# secondary_LTC.net
KiCad netlist of a schematic drawn in Altium Designer
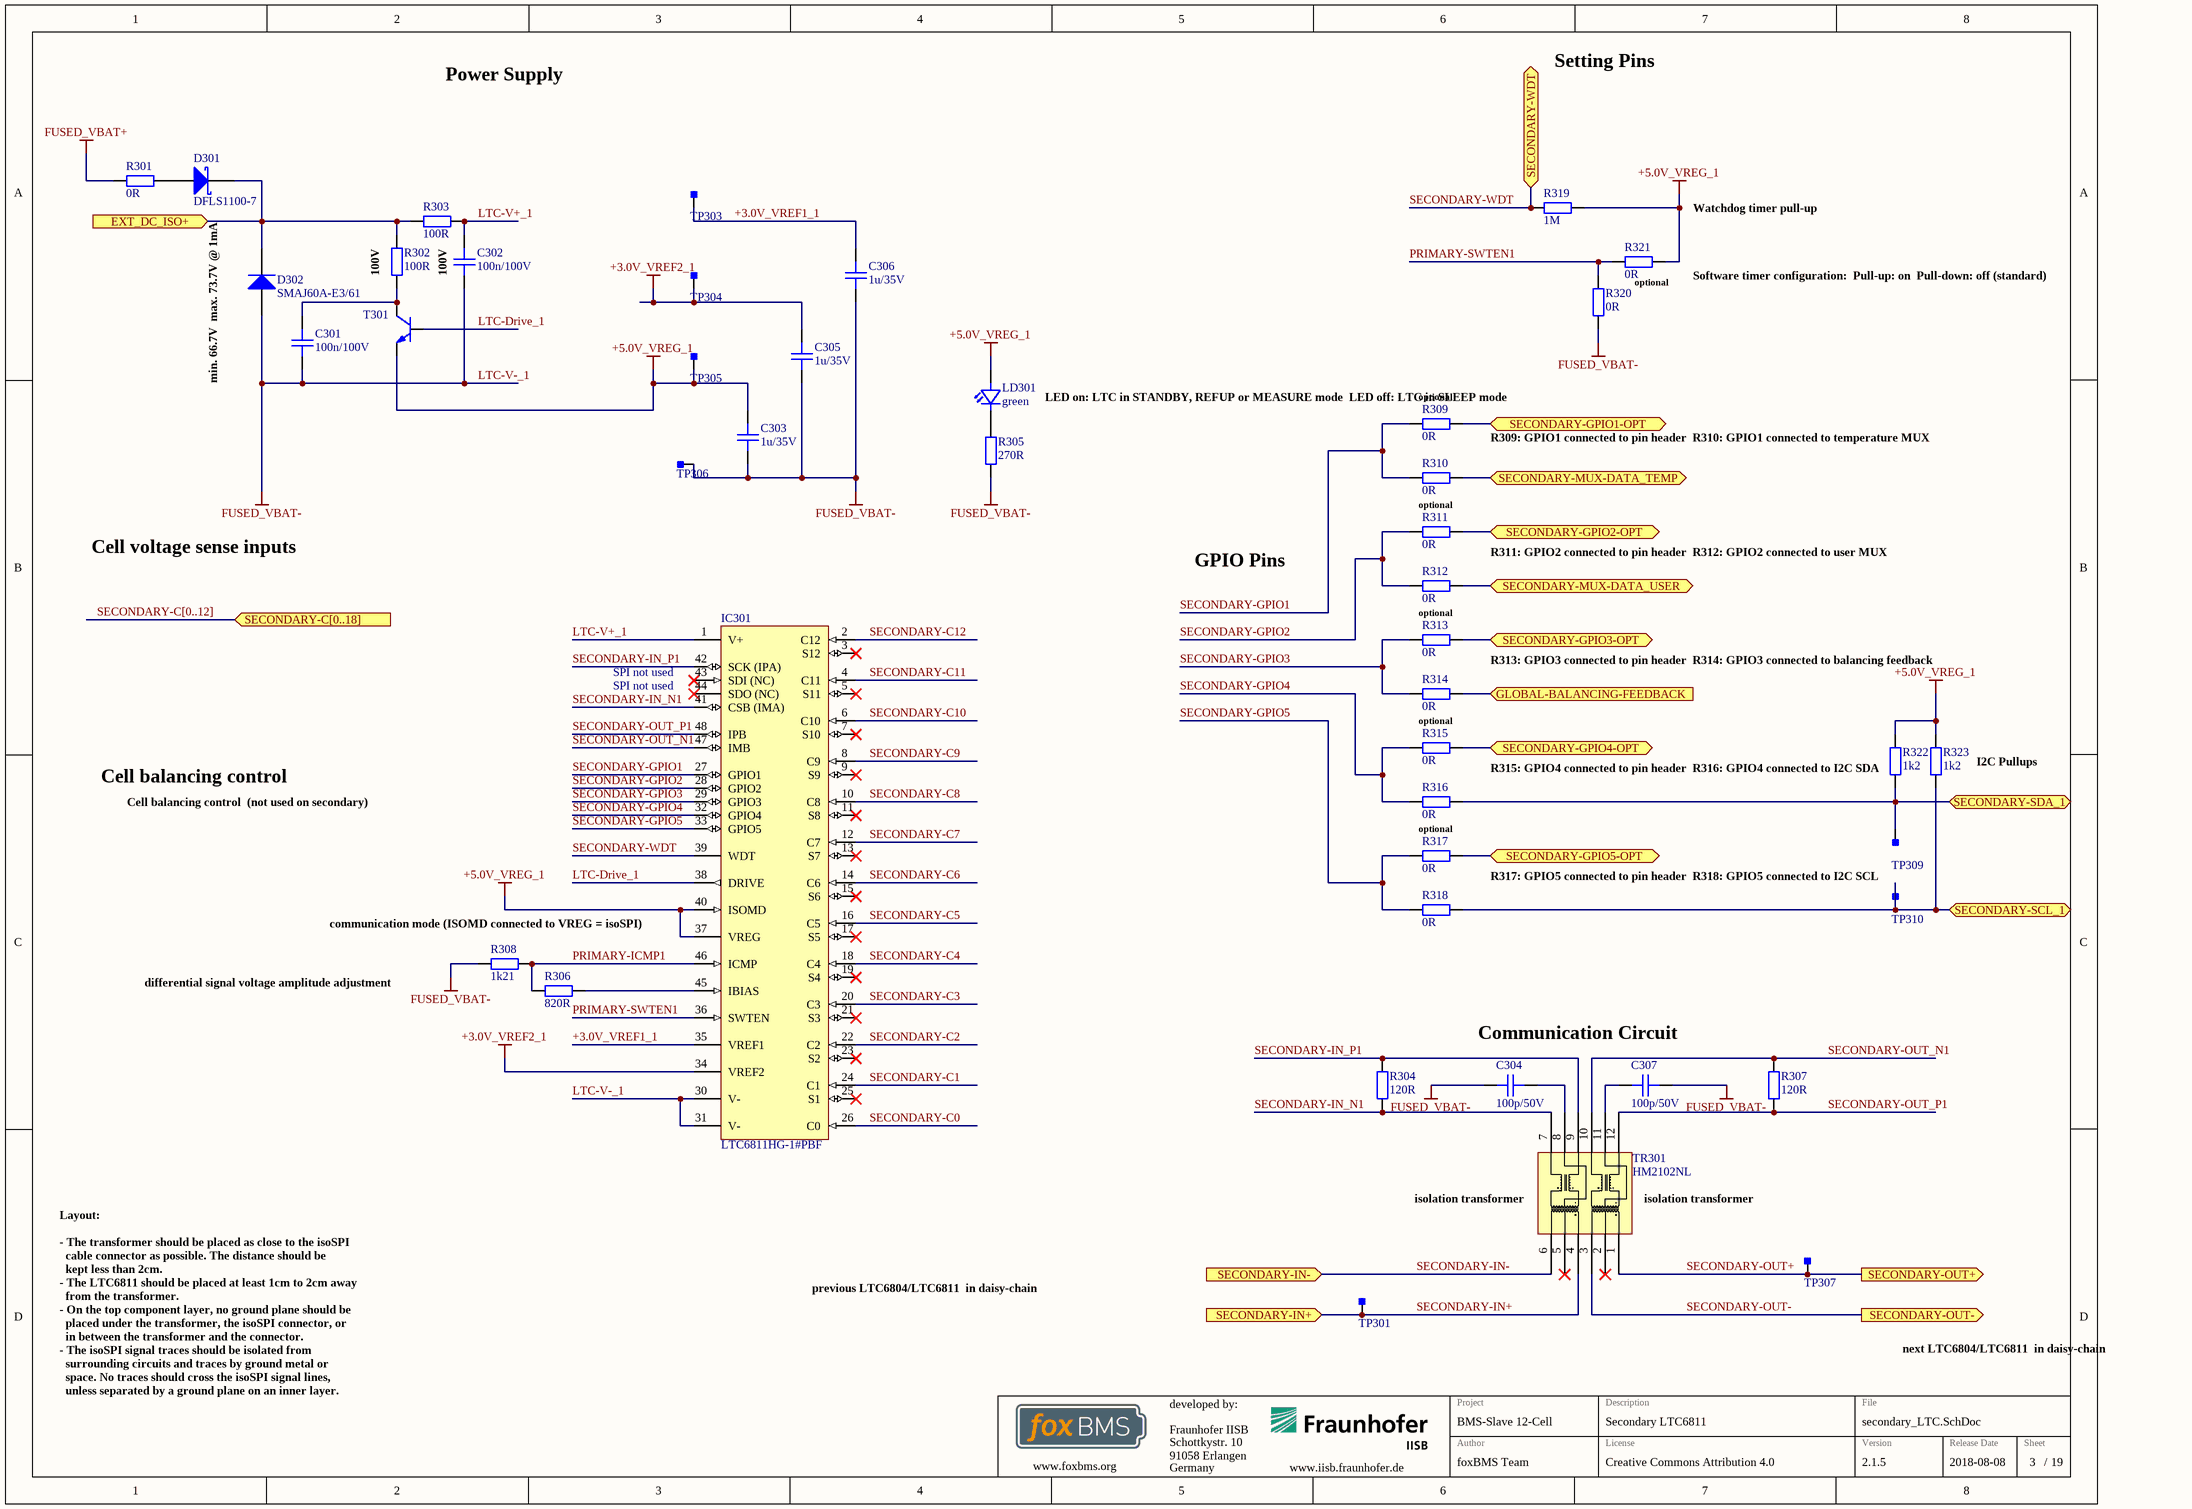
[diagram p0: secondary_LTC.SchDoc]

(export (version "E")
  (design (tool "Eeschema 10.0.6"))
  (components
    (comp (ref "C301")
      (value "100n/100V")
      (footprint "CAPC2012X14N")
      (description "MLCC")
      (fields (field (name "PART NUMBER") "gen_C_ceramic_100n_100V_X7R_0805"))
      (libsource (lib "OE750") (part "C"))
    )
    (comp (ref "C302")
      (value "100n/100V")
      (footprint "CAPC2012X14N")
      (description "MLCC")
      (fields (field (name "PART NUMBER") "gen_C_ceramic_100n_100V_X7R_0805"))
      (libsource (lib "OE750") (part "C"))
    )
    (comp (ref "C303")
      (value "1u/35V")
      (footprint "CAPC1608X08N")
      (description "MLCC")
      (fields (field (name "PART NUMBER") "gen_C_ceramic_1u_35V_X7R_0603"))
      (libsource (lib "OE750") (part "C"))
    )
    (comp (ref "C304")
      (value "100p/50V")
      (footprint "CAPC1608X08N")
      (description "MLCC")
      (fields (field (name "PART NUMBER") "gen_C_ceramic_100p_50V_C0G_0603"))
      (libsource (lib "OE750") (part "C"))
    )
    (comp (ref "C305")
      (value "1u/35V")
      (footprint "CAPC1608X08N")
      (description "MLCC")
      (fields (field (name "PART NUMBER") "gen_C_ceramic_1u_35V_X7R_0603"))
      (libsource (lib "OE750") (part "C"))
    )
    (comp (ref "C306")
      (value "1u/35V")
      (footprint "CAPC1608X08N")
      (description "MLCC")
      (fields (field (name "PART NUMBER") "gen_C_ceramic_1u_35V_X7R_0603"))
      (libsource (lib "OE750") (part "C"))
    )
    (comp (ref "C307")
      (value "100p/50V")
      (footprint "CAPC1608X08N")
      (description "MLCC")
      (fields (field (name "PART NUMBER") "gen_C_ceramic_100p_50V_C0G_0603"))
      (libsource (lib "OE750") (part "C"))
    )
    (comp (ref "D301")
      (value "DFLS1100-7")
      (footprint "DIOD-POWERDI123-2_V")
      (fields (field (name "MANUFACTURER") "Diodes Inc"))
      (libsource (lib "Altium Content Vault") (part "DSKY-AK-2"))
    )
    (comp (ref "D302")
      (value "SMAJ60A-E3/61")
      (footprint "VISH-DO-214AC-2_N")
      (fields (field (name "MANUFACTURER") "Vishay Semiconductor"))
      (libsource (lib "Altium Content Vault") (part "VISH-K1A2-2"))
    )
    (comp (ref "IC301")
      (value "LTC6811HG-1#PBF")
      (footprint "LT-G-48_L")
      (description "Multicell Battery Monitor, 60 V Vin MAX, 48-pin SOP (G-48), -40 to 125 degC, Pb-Free")
      (fields (field (name "MANUFACTURER") "Linear Technology"))
      (libsource (lib "OE750") (part "LTC6811HG-1#PBF"))
    )
    (comp (ref "LD301")
      (value "green")
      (footprint "LEDC1608X07N")
      (description "LED")
      (fields (field (name "PART NUMBER") "gen_LED_0603_green"))
      (libsource (lib "OE750") (part "D_LED"))
    )
    (comp (ref "R301")
      (value "0R")
      (footprint "RESC2012X05N")
      (description "SMD Resistor 0R 0805")
      (fields (field (name "PART NUMBER") "gen_R_0R_0805") (field (name "POWER") "0.125W"))
      (libsource (lib "OE750") (part "R"))
    )
    (comp (ref "R302")
      (value "100R")
      (footprint "RESC2012X05N")
      (description "SMD Resistor 100R 0805")
      (fields (field (name "PART NUMBER") "gen_R_100R_0805") (field (name "TOLERANCE") "1%"))
      (libsource (lib "OE750") (part "R"))
    )
    (comp (ref "R303")
      (value "100R")
      (footprint "RESC2012X05N")
      (description "SMD Resistor 100R 0805")
      (fields (field (name "PART NUMBER") "gen_R_100R_0805") (field (name "TOLERANCE") "1%"))
      (libsource (lib "OE750") (part "R"))
    )
    (comp (ref "R304")
      (value "120R")
      (footprint "RESC1608X05N")
      (description "SMD Resistor 120R 0603")
      (fields (field (name "PART NUMBER") "gen_R_120R_0603") (field (name "TOLERANCE") "1%"))
      (libsource (lib "OE750") (part "R"))
    )
    (comp (ref "R305")
      (value "270R")
      (footprint "RESC1608X05N")
      (description "SMD Resistor 270R 0603")
      (fields (field (name "PART NUMBER") "gen_R_270R_0603") (field (name "TOLERANCE") "1%"))
      (libsource (lib "OE750") (part "R"))
    )
    (comp (ref "R306")
      (value "820R")
      (footprint "RESC1608X05N")
      (description "SMD Resistor 820R 0603")
      (fields (field (name "PART NUMBER") "gen_R_820R_0603") (field (name "TOLERANCE") "1%"))
      (libsource (lib "OE750") (part "R"))
    )
    (comp (ref "R307")
      (value "120R")
      (footprint "RESC1608X05N")
      (description "SMD Resistor 120R 0603")
      (fields (field (name "PART NUMBER") "gen_R_120R_0603") (field (name "TOLERANCE") "1%"))
      (libsource (lib "OE750") (part "R"))
    )
    (comp (ref "R308")
      (value "1k21")
      (footprint "RESC1608X05N")
      (description "SMD Resistor 1k21 0603")
      (fields (field (name "PART NUMBER") "gen_R_1k21_0603") (field (name "TOLERANCE") "1%"))
      (libsource (lib "OE750") (part "R"))
    )
    (comp (ref "R309")
      (value "0R")
      (footprint "RESC1608X05N")
      (description "SMD Resistor 0R 0603")
      (fields (field (name "PART NUMBER") "gen_R_0R_0603") (field (name "POWER") "0.1W"))
      (libsource (lib "OE750") (part "R"))
    )
    (comp (ref "R310")
      (value "0R")
      (footprint "RESC1608X05N")
      (description "SMD Resistor 0R 0603")
      (fields (field (name "PART NUMBER") "gen_R_0R_0603") (field (name "POWER") "0.1W"))
      (libsource (lib "OE750") (part "R"))
    )
    (comp (ref "R311")
      (value "0R")
      (footprint "RESC1608X05N")
      (description "SMD Resistor 0R 0603")
      (fields (field (name "PART NUMBER") "gen_R_0R_0603") (field (name "POWER") "0.1W"))
      (libsource (lib "OE750") (part "R"))
    )
    (comp (ref "R312")
      (value "0R")
      (footprint "RESC1608X05N")
      (description "SMD Resistor 0R 0603")
      (fields (field (name "PART NUMBER") "gen_R_0R_0603") (field (name "POWER") "0.1W"))
      (libsource (lib "OE750") (part "R"))
    )
    (comp (ref "R313")
      (value "0R")
      (footprint "RESC1608X05N")
      (description "SMD Resistor 0R 0603")
      (fields (field (name "PART NUMBER") "gen_R_0R_0603") (field (name "POWER") "0.1W"))
      (libsource (lib "OE750") (part "R"))
    )
    (comp (ref "R314")
      (value "0R")
      (footprint "RESC1608X05N")
      (description "SMD Resistor 0R 0603")
      (fields (field (name "PART NUMBER") "gen_R_0R_0603") (field (name "POWER") "0.1W"))
      (libsource (lib "OE750") (part "R"))
    )
    (comp (ref "R315")
      (value "0R")
      (footprint "RESC1608X05N")
      (description "SMD Resistor 0R 0603")
      (fields (field (name "PART NUMBER") "gen_R_0R_0603") (field (name "POWER") "0.1W"))
      (libsource (lib "OE750") (part "R"))
    )
    (comp (ref "R316")
      (value "0R")
      (footprint "RESC1608X05N")
      (description "SMD Resistor 0R 0603")
      (fields (field (name "PART NUMBER") "gen_R_0R_0603") (field (name "POWER") "0.1W"))
      (libsource (lib "OE750") (part "R"))
    )
    (comp (ref "R317")
      (value "0R")
      (footprint "RESC1608X05N")
      (description "SMD Resistor 0R 0603")
      (fields (field (name "PART NUMBER") "gen_R_0R_0603") (field (name "POWER") "0.1W"))
      (libsource (lib "OE750") (part "R"))
    )
    (comp (ref "R318")
      (value "0R")
      (footprint "RESC1608X05N")
      (description "SMD Resistor 0R 0603")
      (fields (field (name "PART NUMBER") "gen_R_0R_0603") (field (name "POWER") "0.1W"))
      (libsource (lib "OE750") (part "R"))
    )
    (comp (ref "R319")
      (value "1M")
      (footprint "RESC1608X05N")
      (description "SMD Resistor 1M 0603")
      (fields (field (name "PART NUMBER") "gen_R_1M_0603") (field (name "TOLERANCE") "1%"))
      (libsource (lib "OE750") (part "R"))
    )
    (comp (ref "R320")
      (value "0R")
      (footprint "RESC1608X05N")
      (description "SMD Resistor 0R 0603")
      (fields (field (name "PART NUMBER") "gen_R_0R_0603") (field (name "POWER") "0.1W"))
      (libsource (lib "OE750") (part "R"))
    )
    (comp (ref "R321")
      (value "0R")
      (footprint "RESC1608X05N")
      (description "SMD Resistor 0R 0603")
      (fields (field (name "PART NUMBER") "gen_R_0R_0603") (field (name "POWER") "0.1W"))
      (libsource (lib "OE750") (part "R"))
    )
    (comp (ref "R322")
      (value "1k2")
      (footprint "RESC1608X05N")
      (description "SMD Resistor 1k2 0603")
      (fields (field (name "PART NUMBER") "gen_R_1k2_0603") (field (name "TOLERANCE") "1%"))
      (libsource (lib "OE750") (part "R"))
    )
    (comp (ref "R323")
      (value "1k2")
      (footprint "RESC1608X05N")
      (description "SMD Resistor 1k2 0603")
      (fields (field (name "PART NUMBER") "gen_R_1k2_0603") (field (name "TOLERANCE") "1%"))
      (libsource (lib "OE750") (part "R"))
    )
    (comp (ref "T301")
      (value "PBHV8115Z")
      (footprint "SOT230P700X180-4N")
      (description "150 V, 1 A NPN high-voltage low V\r\nCEsat\r\n (BISS) transistor")
      (fields (field (name "MANUFACTURER") "Nexperia"))
      (libsource (lib "OE750") (part "NPN_4_PIN"))
    )
    (comp (ref "TP301")
      (value "Testpoint_Square")
      (footprint "Testpoint_S1")
      (description "Testpoint, square")
      (libsource (lib "OE750") (part "Testpoint_Square"))
    )
    (comp (ref "TP303")
      (value "Testpoint_Square")
      (footprint "Testpoint_S1")
      (description "Testpoint, square")
      (libsource (lib "OE750") (part "Testpoint_Square"))
    )
    (comp (ref "TP304")
      (value "Testpoint_Square")
      (footprint "Testpoint_S1")
      (description "Testpoint, square")
      (libsource (lib "OE750") (part "Testpoint_Square"))
    )
    (comp (ref "TP305")
      (value "Testpoint_Square")
      (footprint "Testpoint_S1")
      (description "Testpoint, square")
      (libsource (lib "OE750") (part "Testpoint_Square"))
    )
    (comp (ref "TP306")
      (value "Testpoint_Square")
      (footprint "Testpoint_S1")
      (description "Testpoint, square")
      (libsource (lib "OE750") (part "Testpoint_Square"))
    )
    (comp (ref "TP307")
      (value "Testpoint_Square")
      (footprint "Testpoint_S1")
      (description "Testpoint, square")
      (libsource (lib "OE750") (part "Testpoint_Square"))
    )
    (comp (ref "TP309")
      (value "Testpoint_Square")
      (footprint "Testpoint_S1")
      (description "Testpoint, square")
      (libsource (lib "OE750") (part "Testpoint_Square"))
    )
    (comp (ref "TP310")
      (value "Testpoint_Square")
      (footprint "Testpoint_S1")
      (description "Testpoint, square")
      (libsource (lib "OE750") (part "Testpoint_Square"))
    )
    (comp (ref "TR301")
      (value "HM2102NL")
      (footprint "HM2102NL")
      (description "Pulse HM2102NL BMS Transformer")
      (fields (field (name "MANUFACTURER") "Pulse"))
      (libsource (lib "OE750") (part "HM2102NL"))
    )
  )
  (nets
    (net (code "1") (name "+3.0V_VREF2_1") (class "Default")
      (node (ref "C305") (pin "2") (pinfunction "2_2") (pintype "passive"))
      (node (ref "IC301") (pin "34") (pinfunction "VREF2_34") (pintype "passive"))
      (node (ref "TP304") (pin "1") (pinfunction "1_1") (pintype "passive"))
    )
    (net (code "2") (name "+5.0V_VREG_1") (class "Default")
      (node (ref "C303") (pin "2") (pinfunction "2_2") (pintype "passive"))
      (node (ref "IC301") (pin "37") (pinfunction "VREG_37") (pintype "power_in"))
      (node (ref "IC301") (pin "40") (pinfunction "ISOMD_40") (pintype "input"))
      (node (ref "LD301") (pin "2") (pinfunction "A_2") (pintype "passive"))
      (node (ref "R319") (pin "2") (pinfunction "2_2") (pintype "passive"))
      (node (ref "R321") (pin "2") (pinfunction "2_2") (pintype "passive"))
      (node (ref "R322") (pin "2") (pinfunction "2_2") (pintype "passive"))
      (node (ref "R323") (pin "2") (pinfunction "2_2") (pintype "passive"))
      (node (ref "T301") (pin "3") (pinfunction "E_3") (pintype "passive"))
      (node (ref "TP305") (pin "1") (pinfunction "1_1") (pintype "passive"))
    )
    (net (code "3") (name "/+3.0V_VREF1_1") (class "Default")
      (node (ref "C306") (pin "2") (pinfunction "2_2") (pintype "passive"))
      (node (ref "IC301") (pin "35") (pinfunction "VREF1_35") (pintype "passive"))
      (node (ref "TP303") (pin "1") (pinfunction "1_1") (pintype "passive"))
    )
    (net (code "4") (name "/EXT_DC_ISO+") (class "Default")
      (node (ref "D301") (pin "2") (pinfunction "K_2") (pintype "passive"))
      (node (ref "D302") (pin "1") (pinfunction "K_1") (pintype "passive"))
      (node (ref "R302") (pin "2") (pinfunction "2_2") (pintype "passive"))
      (node (ref "R303") (pin "1") (pinfunction "1_1") (pintype "passive"))
    )
    (net (code "5") (name "/GLOBAL-BALANCING-FEEDBACK") (class "Default")
      (node (ref "R314") (pin "1") (pinfunction "1_1") (pintype "passive"))
    )
    (net (code "6") (name "/LTC-Drive_1") (class "Default")
      (node (ref "IC301") (pin "38") (pinfunction "DRIVE_38") (pintype "output"))
      (node (ref "T301") (pin "1") (pinfunction "B_1") (pintype "passive"))
    )
    (net (code "7") (name "/LTC-V+_1") (class "Default")
      (node (ref "C302") (pin "1") (pinfunction "1_1") (pintype "passive"))
      (node (ref "IC301") (pin "1") (pinfunction "V+_1") (pintype "power_in"))
      (node (ref "R303") (pin "2") (pinfunction "2_2") (pintype "passive"))
    )
    (net (code "8") (name "/PRIMARY-ICMP1") (class "Default")
      (node (ref "IC301") (pin "46") (pinfunction "ICMP_46") (pintype "input"))
      (node (ref "R306") (pin "1") (pinfunction "1_1") (pintype "passive"))
      (node (ref "R308") (pin "2") (pinfunction "2_2") (pintype "passive"))
    )
    (net (code "9") (name "/PRIMARY-SWTEN1") (class "Default")
      (node (ref "IC301") (pin "36") (pinfunction "SWTEN_36") (pintype "input"))
      (node (ref "R320") (pin "2") (pinfunction "2_2") (pintype "passive"))
      (node (ref "R321") (pin "1") (pinfunction "1_1") (pintype "passive"))
    )
    (net (code "10") (name "/SECONDARY-C0") (class "Default")
      (node (ref "IC301") (pin "26") (pinfunction "C0_26") (pintype "input"))
    )
    (net (code "11") (name "/SECONDARY-C1") (class "Default")
      (node (ref "IC301") (pin "24") (pinfunction "C1_24") (pintype "input"))
    )
    (net (code "12") (name "/SECONDARY-C2") (class "Default")
      (node (ref "IC301") (pin "22") (pinfunction "C2_22") (pintype "input"))
    )
    (net (code "13") (name "/SECONDARY-C3") (class "Default")
      (node (ref "IC301") (pin "20") (pinfunction "C3_20") (pintype "input"))
    )
    (net (code "14") (name "/SECONDARY-C4") (class "Default")
      (node (ref "IC301") (pin "18") (pinfunction "C4_18") (pintype "input"))
    )
    (net (code "15") (name "/SECONDARY-C5") (class "Default")
      (node (ref "IC301") (pin "16") (pinfunction "C5_16") (pintype "input"))
    )
    (net (code "16") (name "/SECONDARY-C6") (class "Default")
      (node (ref "IC301") (pin "14") (pinfunction "C6_14") (pintype "input"))
    )
    (net (code "17") (name "/SECONDARY-C7") (class "Default")
      (node (ref "IC301") (pin "12") (pinfunction "C7_12") (pintype "input"))
    )
    (net (code "18") (name "/SECONDARY-C8") (class "Default")
      (node (ref "IC301") (pin "10") (pinfunction "C8_10") (pintype "input"))
    )
    (net (code "19") (name "/SECONDARY-C9") (class "Default")
      (node (ref "IC301") (pin "8") (pinfunction "C9_8") (pintype "input"))
    )
    (net (code "20") (name "/SECONDARY-C10") (class "Default")
      (node (ref "IC301") (pin "6") (pinfunction "C10_6") (pintype "input"))
    )
    (net (code "21") (name "/SECONDARY-C11") (class "Default")
      (node (ref "IC301") (pin "4") (pinfunction "C11_4") (pintype "input"))
    )
    (net (code "22") (name "/SECONDARY-C12") (class "Default")
      (node (ref "IC301") (pin "2") (pinfunction "C12_2") (pintype "input"))
    )
    (net (code "24") (name "/SECONDARY-GPIO1") (class "Default")
      (node (ref "IC301") (pin "27") (pinfunction "GPIO1_27") (pintype "bidirectional"))
      (node (ref "R309") (pin "2") (pinfunction "2_2") (pintype "passive"))
      (node (ref "R310") (pin "2") (pinfunction "2_2") (pintype "passive"))
    )
    (net (code "25") (name "/SECONDARY-GPIO1-OPT") (class "Default")
      (node (ref "R309") (pin "1") (pinfunction "1_1") (pintype "passive"))
    )
    (net (code "26") (name "/SECONDARY-GPIO2") (class "Default")
      (node (ref "IC301") (pin "28") (pinfunction "GPIO2_28") (pintype "bidirectional"))
      (node (ref "R311") (pin "2") (pinfunction "2_2") (pintype "passive"))
      (node (ref "R312") (pin "2") (pinfunction "2_2") (pintype "passive"))
    )
    (net (code "27") (name "/SECONDARY-GPIO2-OPT") (class "Default")
      (node (ref "R311") (pin "1") (pinfunction "1_1") (pintype "passive"))
    )
    (net (code "28") (name "/SECONDARY-GPIO3") (class "Default")
      (node (ref "IC301") (pin "29") (pinfunction "GPIO3_29") (pintype "bidirectional"))
      (node (ref "R313") (pin "2") (pinfunction "2_2") (pintype "passive"))
      (node (ref "R314") (pin "2") (pinfunction "2_2") (pintype "passive"))
    )
    (net (code "29") (name "/SECONDARY-GPIO3-OPT") (class "Default")
      (node (ref "R313") (pin "1") (pinfunction "1_1") (pintype "passive"))
    )
    (net (code "30") (name "/SECONDARY-GPIO4") (class "Default")
      (node (ref "IC301") (pin "32") (pinfunction "GPIO4_32") (pintype "bidirectional"))
      (node (ref "R315") (pin "2") (pinfunction "2_2") (pintype "passive"))
      (node (ref "R316") (pin "2") (pinfunction "2_2") (pintype "passive"))
    )
    (net (code "31") (name "/SECONDARY-GPIO4-OPT") (class "Default")
      (node (ref "R315") (pin "1") (pinfunction "1_1") (pintype "passive"))
    )
    (net (code "32") (name "/SECONDARY-GPIO5") (class "Default")
      (node (ref "IC301") (pin "33") (pinfunction "GPIO5_33") (pintype "bidirectional"))
      (node (ref "R317") (pin "2") (pinfunction "2_2") (pintype "passive"))
      (node (ref "R318") (pin "2") (pinfunction "2_2") (pintype "passive"))
    )
    (net (code "33") (name "/SECONDARY-GPIO5-OPT") (class "Default")
      (node (ref "R317") (pin "1") (pinfunction "1_1") (pintype "passive"))
    )
    (net (code "34") (name "/SECONDARY-IN+") (class "Default")
      (node (ref "TP301") (pin "1") (pinfunction "1_1") (pintype "passive"))
      (node (ref "TR301") (pin "4") (pintype "passive"))
    )
    (net (code "35") (name "/SECONDARY-IN-") (class "Default")
      (node (ref "TR301") (pin "6") (pintype "passive"))
    )
    (net (code "36") (name "/SECONDARY-IN_N1") (class "Default")
      (node (ref "IC301") (pin "41") (pinfunction "CSB_(IMA)_41") (pintype "bidirectional"))
      (node (ref "R304") (pin "2") (pinfunction "2_2") (pintype "passive"))
      (node (ref "TR301") (pin "7") (pintype "passive"))
    )
    (net (code "37") (name "/SECONDARY-IN_P1") (class "Default")
      (node (ref "IC301") (pin "42") (pinfunction "SCK_(IPA)_42") (pintype "bidirectional"))
      (node (ref "R304") (pin "1") (pinfunction "1_1") (pintype "passive"))
      (node (ref "TR301") (pin "9") (pintype "passive"))
    )
    (net (code "38") (name "/SECONDARY-MUX-DATA_TEMP") (class "Default")
      (node (ref "R310") (pin "1") (pinfunction "1_1") (pintype "passive"))
    )
    (net (code "39") (name "/SECONDARY-MUX-DATA_USER") (class "Default")
      (node (ref "R312") (pin "1") (pinfunction "1_1") (pintype "passive"))
    )
    (net (code "40") (name "/SECONDARY-OUT+") (class "Default")
      (node (ref "TP307") (pin "1") (pinfunction "1_1") (pintype "passive"))
      (node (ref "TR301") (pin "1") (pintype "passive"))
    )
    (net (code "41") (name "/SECONDARY-OUT-") (class "Default")
      (node (ref "TR301") (pin "3") (pintype "passive"))
    )
    (net (code "42") (name "/SECONDARY-OUT_N1") (class "Default")
      (node (ref "IC301") (pin "47") (pinfunction "IMB_47") (pintype "bidirectional"))
      (node (ref "R307") (pin "2") (pinfunction "2_2") (pintype "passive"))
      (node (ref "TR301") (pin "10") (pintype "passive"))
    )
    (net (code "43") (name "/SECONDARY-OUT_P1") (class "Default")
      (node (ref "IC301") (pin "48") (pinfunction "IPB_48") (pintype "bidirectional"))
      (node (ref "R307") (pin "1") (pinfunction "1_1") (pintype "passive"))
      (node (ref "TR301") (pin "12") (pintype "passive"))
    )
    (net (code "44") (name "/SECONDARY-SCL_1") (class "Default")
      (node (ref "R318") (pin "1") (pinfunction "1_1") (pintype "passive"))
      (node (ref "R323") (pin "1") (pinfunction "1_1") (pintype "passive"))
      (node (ref "TP310") (pin "1") (pinfunction "1_1") (pintype "passive"))
    )
    (net (code "45") (name "/SECONDARY-SDA_1") (class "Default")
      (node (ref "R316") (pin "1") (pinfunction "1_1") (pintype "passive"))
      (node (ref "R322") (pin "1") (pinfunction "1_1") (pintype "passive"))
      (node (ref "TP309") (pin "1") (pinfunction "1_1") (pintype "passive"))
    )
    (net (code "46") (name "/SECONDARY-WDT") (class "Default")
      (node (ref "IC301") (pin "39") (pinfunction "WDT_39") (pintype "tri_state"))
      (node (ref "R319") (pin "1") (pinfunction "1_1") (pintype "passive"))
    )
    (net (code "47") (name "FUSED_VBAT+") (class "Default")
      (node (ref "R301") (pin "1") (pinfunction "1_1") (pintype "passive"))
    )
    (net (code "48") (name "FUSED_VBAT-") (class "Default")
      (node (ref "C301") (pin "2") (pinfunction "2_2") (pintype "passive"))
      (node (ref "C302") (pin "2") (pinfunction "2_2") (pintype "passive"))
      (node (ref "C303") (pin "1") (pinfunction "1_1") (pintype "passive"))
      (node (ref "C304") (pin "1") (pinfunction "1_1") (pintype "passive"))
      (node (ref "C305") (pin "1") (pinfunction "1_1") (pintype "passive"))
      (node (ref "C306") (pin "1") (pinfunction "1_1") (pintype "passive"))
      (node (ref "C307") (pin "1") (pinfunction "1_1") (pintype "passive"))
      (node (ref "D302") (pin "2") (pinfunction "A_2") (pintype "passive"))
      (node (ref "IC301") (pin "30") (pinfunction "V-_30") (pintype "power_in"))
      (node (ref "IC301") (pin "31") (pinfunction "V-_31") (pintype "power_in"))
      (node (ref "R305") (pin "1") (pinfunction "1_1") (pintype "passive"))
      (node (ref "R308") (pin "1") (pinfunction "1_1") (pintype "passive"))
      (node (ref "R320") (pin "1") (pinfunction "1_1") (pintype "passive"))
      (node (ref "TP306") (pin "1") (pinfunction "1_1") (pintype "passive"))
    )
    (net (code "49") (name "Net-(C301-Pad1)") (class "Default")
      (node (ref "C301") (pin "1") (pinfunction "1_1") (pintype "passive"))
      (node (ref "R302") (pin "1") (pinfunction "1_1") (pintype "passive"))
      (node (ref "T301") (pin "2") (pinfunction "C_2") (pintype "passive"))
      (node (ref "T301") (pin "4") (pinfunction "C_4") (pintype "passive"))
    )
    (net (code "50") (name "Net-(C304-Pad2)") (class "Default")
      (node (ref "C304") (pin "2") (pinfunction "2_2") (pintype "passive"))
      (node (ref "TR301") (pin "8") (pintype "passive"))
    )
    (net (code "51") (name "Net-(C307-Pad2)") (class "Default")
      (node (ref "C307") (pin "2") (pinfunction "2_2") (pintype "passive"))
      (node (ref "TR301") (pin "11") (pintype "passive"))
    )
    (net (code "52") (name "Net-(D301-A)") (class "Default")
      (node (ref "D301") (pin "1") (pinfunction "A_1") (pintype "passive"))
      (node (ref "R301") (pin "2") (pinfunction "2_2") (pintype "passive"))
    )
    (net (code "53") (name "Net-(IC301-IBIAS)") (class "Default")
      (node (ref "IC301") (pin "45") (pinfunction "IBIAS_45") (pintype "input"))
      (node (ref "R306") (pin "2") (pinfunction "2_2") (pintype "passive"))
    )
    (net (code "54") (name "Net-(LD301-C)") (class "Default")
      (node (ref "LD301") (pin "1") (pinfunction "C_1") (pintype "passive"))
      (node (ref "R305") (pin "2") (pinfunction "2_2") (pintype "passive"))
    )
    (net (code "55") (name "unconnected-(IC301-S1-Pad25)") (class "Default")
      (node (ref "IC301") (pin "25") (pinfunction "S1_25") (pintype "bidirectional+no_connect"))
    )
    (net (code "56") (name "unconnected-(IC301-S2-Pad23)") (class "Default")
      (node (ref "IC301") (pin "23") (pinfunction "S2_23") (pintype "bidirectional+no_connect"))
    )
    (net (code "57") (name "unconnected-(IC301-S3-Pad21)") (class "Default")
      (node (ref "IC301") (pin "21") (pinfunction "S3_21") (pintype "bidirectional+no_connect"))
    )
    (net (code "58") (name "unconnected-(IC301-S4-Pad19)") (class "Default")
      (node (ref "IC301") (pin "19") (pinfunction "S4_19") (pintype "bidirectional+no_connect"))
    )
    (net (code "59") (name "unconnected-(IC301-S5-Pad17)") (class "Default")
      (node (ref "IC301") (pin "17") (pinfunction "S5_17") (pintype "bidirectional+no_connect"))
    )
    (net (code "60") (name "unconnected-(IC301-S6-Pad15)") (class "Default")
      (node (ref "IC301") (pin "15") (pinfunction "S6_15") (pintype "bidirectional+no_connect"))
    )
    (net (code "61") (name "unconnected-(IC301-S7-Pad13)") (class "Default")
      (node (ref "IC301") (pin "13") (pinfunction "S7_13") (pintype "bidirectional+no_connect"))
    )
    (net (code "62") (name "unconnected-(IC301-S8-Pad11)") (class "Default")
      (node (ref "IC301") (pin "11") (pinfunction "S8_11") (pintype "bidirectional+no_connect"))
    )
    (net (code "63") (name "unconnected-(IC301-S9-Pad9)") (class "Default")
      (node (ref "IC301") (pin "9") (pinfunction "S9_9") (pintype "bidirectional+no_connect"))
    )
    (net (code "64") (name "unconnected-(IC301-S10-Pad7)") (class "Default")
      (node (ref "IC301") (pin "7") (pinfunction "S10_7") (pintype "bidirectional+no_connect"))
    )
    (net (code "65") (name "unconnected-(IC301-S11-Pad5)") (class "Default")
      (node (ref "IC301") (pin "5") (pinfunction "S11_5") (pintype "bidirectional+no_connect"))
    )
    (net (code "66") (name "unconnected-(IC301-S12-Pad3)") (class "Default")
      (node (ref "IC301") (pin "3") (pinfunction "S12_3") (pintype "bidirectional+no_connect"))
    )
    (net (code "67") (name "unconnected-(IC301-SDI_(NC)-Pad43)") (class "Default")
      (node (ref "IC301") (pin "43") (pinfunction "SDI_(NC)_43") (pintype "input+no_connect"))
    )
    (net (code "68") (name "unconnected-(IC301-SDO_(NC)-Pad44)") (class "Default")
      (node (ref "IC301") (pin "44") (pinfunction "SDO_(NC)_44") (pintype "open_collector+no_connect"))
    )
    (net (code "69") (name "unconnected-(TR301-Pad2)") (class "Default")
      (node (ref "TR301") (pin "2") (pintype "passive+no_connect"))
    )
    (net (code "70") (name "unconnected-(TR301-Pad5)") (class "Default")
      (node (ref "TR301") (pin "5") (pintype "passive+no_connect"))
    )
  )
)
